# LoRaModule.net
KiCad netlist of a schematic drawn in Altium Designer
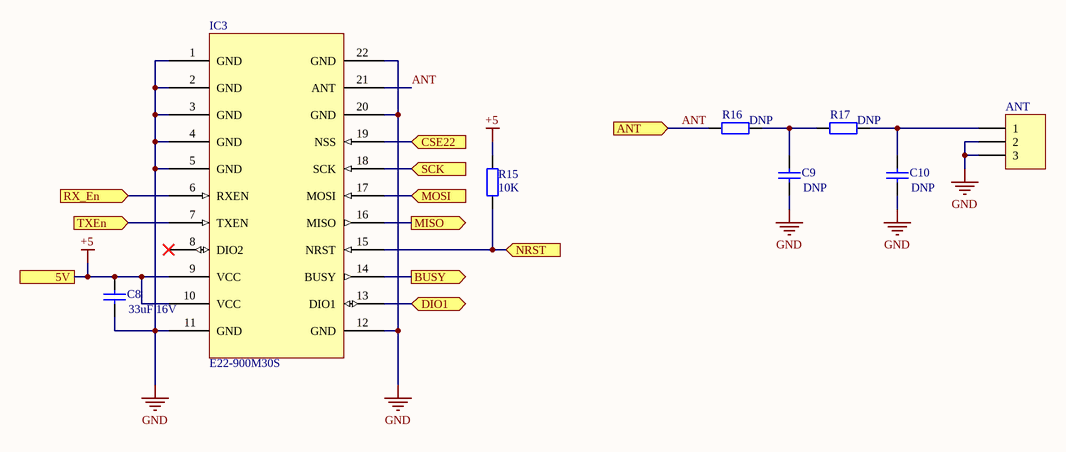
[diagram p0: LoRaModule.SchDoc]

(export (version "E")
  (design (tool "Eeschema 10.0.6"))
  (components
    (comp (ref "ANT")
      (value "Header 3")
      (footprint "IPEX Board Conn")
      (description "Header, 3-Pin")
      (fields (field (name "LCSC PART #") "C88374") (field (name "PUBLISHER") "Altium Limited"))
      (libsource (lib "Miscellaneous Connectors") (part "Header 3"))
    )
    (comp (ref "C8")
      (value "33uF 16V")
      (footprint "RES 1206")
      (description "Capacitor")
      (fields (field (name "Comment") "Cap") (field (name "PUBLISHER") "Altium Limited"))
      (libsource (lib "Miscellaneous Devices") (part "Cap"))
    )
    (comp (ref "C9")
      (value "DNP")
      (footprint "CAP0805")
      (description "Capacitor")
      (fields (field (name "Comment") "Cap") (field (name "PUBLISHER") "Altium Limited"))
      (libsource (lib "Miscellaneous Devices") (part "Cap"))
    )
    (comp (ref "C10")
      (value "DNP")
      (footprint "CAP0805")
      (description "Capacitor")
      (fields (field (name "Comment") "Cap") (field (name "PUBLISHER") "Altium Limited"))
      (libsource (lib "Miscellaneous Devices") (part "Cap"))
    )
    (comp (ref "IC3")
      (value "E22-900M30S")
      (footprint "E22-900M30S")
      (libsource (lib "E22-900M30S") (part "E22-900M30S"))
    )
    (comp (ref "R15")
      (value "10K")
      (footprint "RES0805")
      (description "Resistor")
      (fields
        (field (name "LCSC PART #") "C2930231")
        (field (name "Comment") "Res2")
        (field (name "PUBLISHER") "Altium Limited")
      )
      (libsource (lib "Miscellaneous Devices") (part "Res2"))
    )
    (comp (ref "R16")
      (value "DNP")
      (footprint "RES0805")
      (description "Resistor")
      (fields (field (name "Comment") "Res2") (field (name "PUBLISHER") "Altium Limited"))
      (libsource (lib "") (part "Res2_1"))
    )
    (comp (ref "R17")
      (value "DNP")
      (footprint "RES0805")
      (description "Resistor")
      (fields (field (name "Comment") "Res2") (field (name "PUBLISHER") "Altium Limited"))
      (libsource (lib "") (part "Res2_1"))
    )
  )
  (nets
    (net (code "1") (name "+5") (class "Default")
      (node (ref "C8") (pin "2") (pinfunction "2_2") (pintype "passive"))
      (node (ref "IC3") (pin "10") (pinfunction "VCC_10") (pintype "power_in"))
      (node (ref "IC3") (pin "9") (pinfunction "VCC_9") (pintype "power_in"))
      (node (ref "R15") (pin "2") (pinfunction "2_2") (pintype "passive"))
    )
    (net (code "2") (name "/ANT") (class "Default")
      (node (ref "IC3") (pin "21") (pinfunction "ANT_21") (pintype "passive"))
      (node (ref "R16") (pin "1") (pinfunction "1_1") (pintype "passive"))
    )
    (net (code "3") (name "/BUSY") (class "Default")
      (node (ref "IC3") (pin "14") (pinfunction "BUSY_14") (pintype "output"))
    )
    (net (code "4") (name "/CSE22") (class "Default")
      (node (ref "IC3") (pin "19") (pinfunction "NSS_19") (pintype "input"))
    )
    (net (code "5") (name "/DIO1") (class "Default")
      (node (ref "IC3") (pin "13") (pinfunction "DIO1_13") (pintype "bidirectional"))
    )
    (net (code "6") (name "/MISO") (class "Default")
      (node (ref "IC3") (pin "16") (pinfunction "MISO_16") (pintype "output"))
    )
    (net (code "7") (name "/MOSI") (class "Default")
      (node (ref "IC3") (pin "17") (pinfunction "MOSI_17") (pintype "input"))
    )
    (net (code "8") (name "/NRST") (class "Default")
      (node (ref "IC3") (pin "15") (pinfunction "NRST_15") (pintype "input"))
      (node (ref "R15") (pin "1") (pinfunction "1_1") (pintype "passive"))
    )
    (net (code "9") (name "/RX_En") (class "Default")
      (node (ref "IC3") (pin "6") (pinfunction "RXEN_6") (pintype "input"))
    )
    (net (code "10") (name "/SCK") (class "Default")
      (node (ref "IC3") (pin "18") (pinfunction "SCK_18") (pintype "input"))
    )
    (net (code "11") (name "/TXEn") (class "Default")
      (node (ref "IC3") (pin "7") (pinfunction "TXEN_7") (pintype "input"))
    )
    (net (code "12") (name "GND") (class "Default")
      (node (ref "ANT") (pin "2") (pinfunction "2_2") (pintype "passive"))
      (node (ref "ANT") (pin "3") (pinfunction "3_3") (pintype "passive"))
      (node (ref "C10") (pin "1") (pinfunction "1_1") (pintype "passive"))
      (node (ref "C8") (pin "1") (pinfunction "1_1") (pintype "passive"))
      (node (ref "C9") (pin "1") (pinfunction "1_1") (pintype "passive"))
      (node (ref "IC3") (pin "1") (pinfunction "GND_1") (pintype "passive"))
      (node (ref "IC3") (pin "11") (pinfunction "GND_11") (pintype "passive"))
      (node (ref "IC3") (pin "12") (pinfunction "GND_12") (pintype "passive"))
      (node (ref "IC3") (pin "2") (pinfunction "GND_2") (pintype "passive"))
      (node (ref "IC3") (pin "20") (pinfunction "GND_20") (pintype "passive"))
      (node (ref "IC3") (pin "22") (pinfunction "GND_22") (pintype "passive"))
      (node (ref "IC3") (pin "3") (pinfunction "GND_3") (pintype "passive"))
      (node (ref "IC3") (pin "4") (pinfunction "GND_4") (pintype "passive"))
      (node (ref "IC3") (pin "5") (pinfunction "GND_5") (pintype "passive"))
    )
    (net (code "13") (name "Net-(ANT-Pad1)") (class "Default")
      (node (ref "ANT") (pin "1") (pinfunction "1_1") (pintype "passive"))
      (node (ref "C10") (pin "2") (pinfunction "2_2") (pintype "passive"))
      (node (ref "R17") (pin "2") (pinfunction "2_2") (pintype "passive"))
    )
    (net (code "14") (name "Net-(C9-Pad2)") (class "Default")
      (node (ref "C9") (pin "2") (pinfunction "2_2") (pintype "passive"))
      (node (ref "R16") (pin "2") (pinfunction "2_2") (pintype "passive"))
      (node (ref "R17") (pin "1") (pinfunction "1_1") (pintype "passive"))
    )
    (net (code "15") (name "unconnected-(IC3-DIO2-Pad8)") (class "Default")
      (node (ref "IC3") (pin "8") (pinfunction "DIO2_8") (pintype "bidirectional+no_connect"))
    )
  )
)
